# sch_station_de_charge.net
KiCad netlist of a schematic drawn in Altium Designer
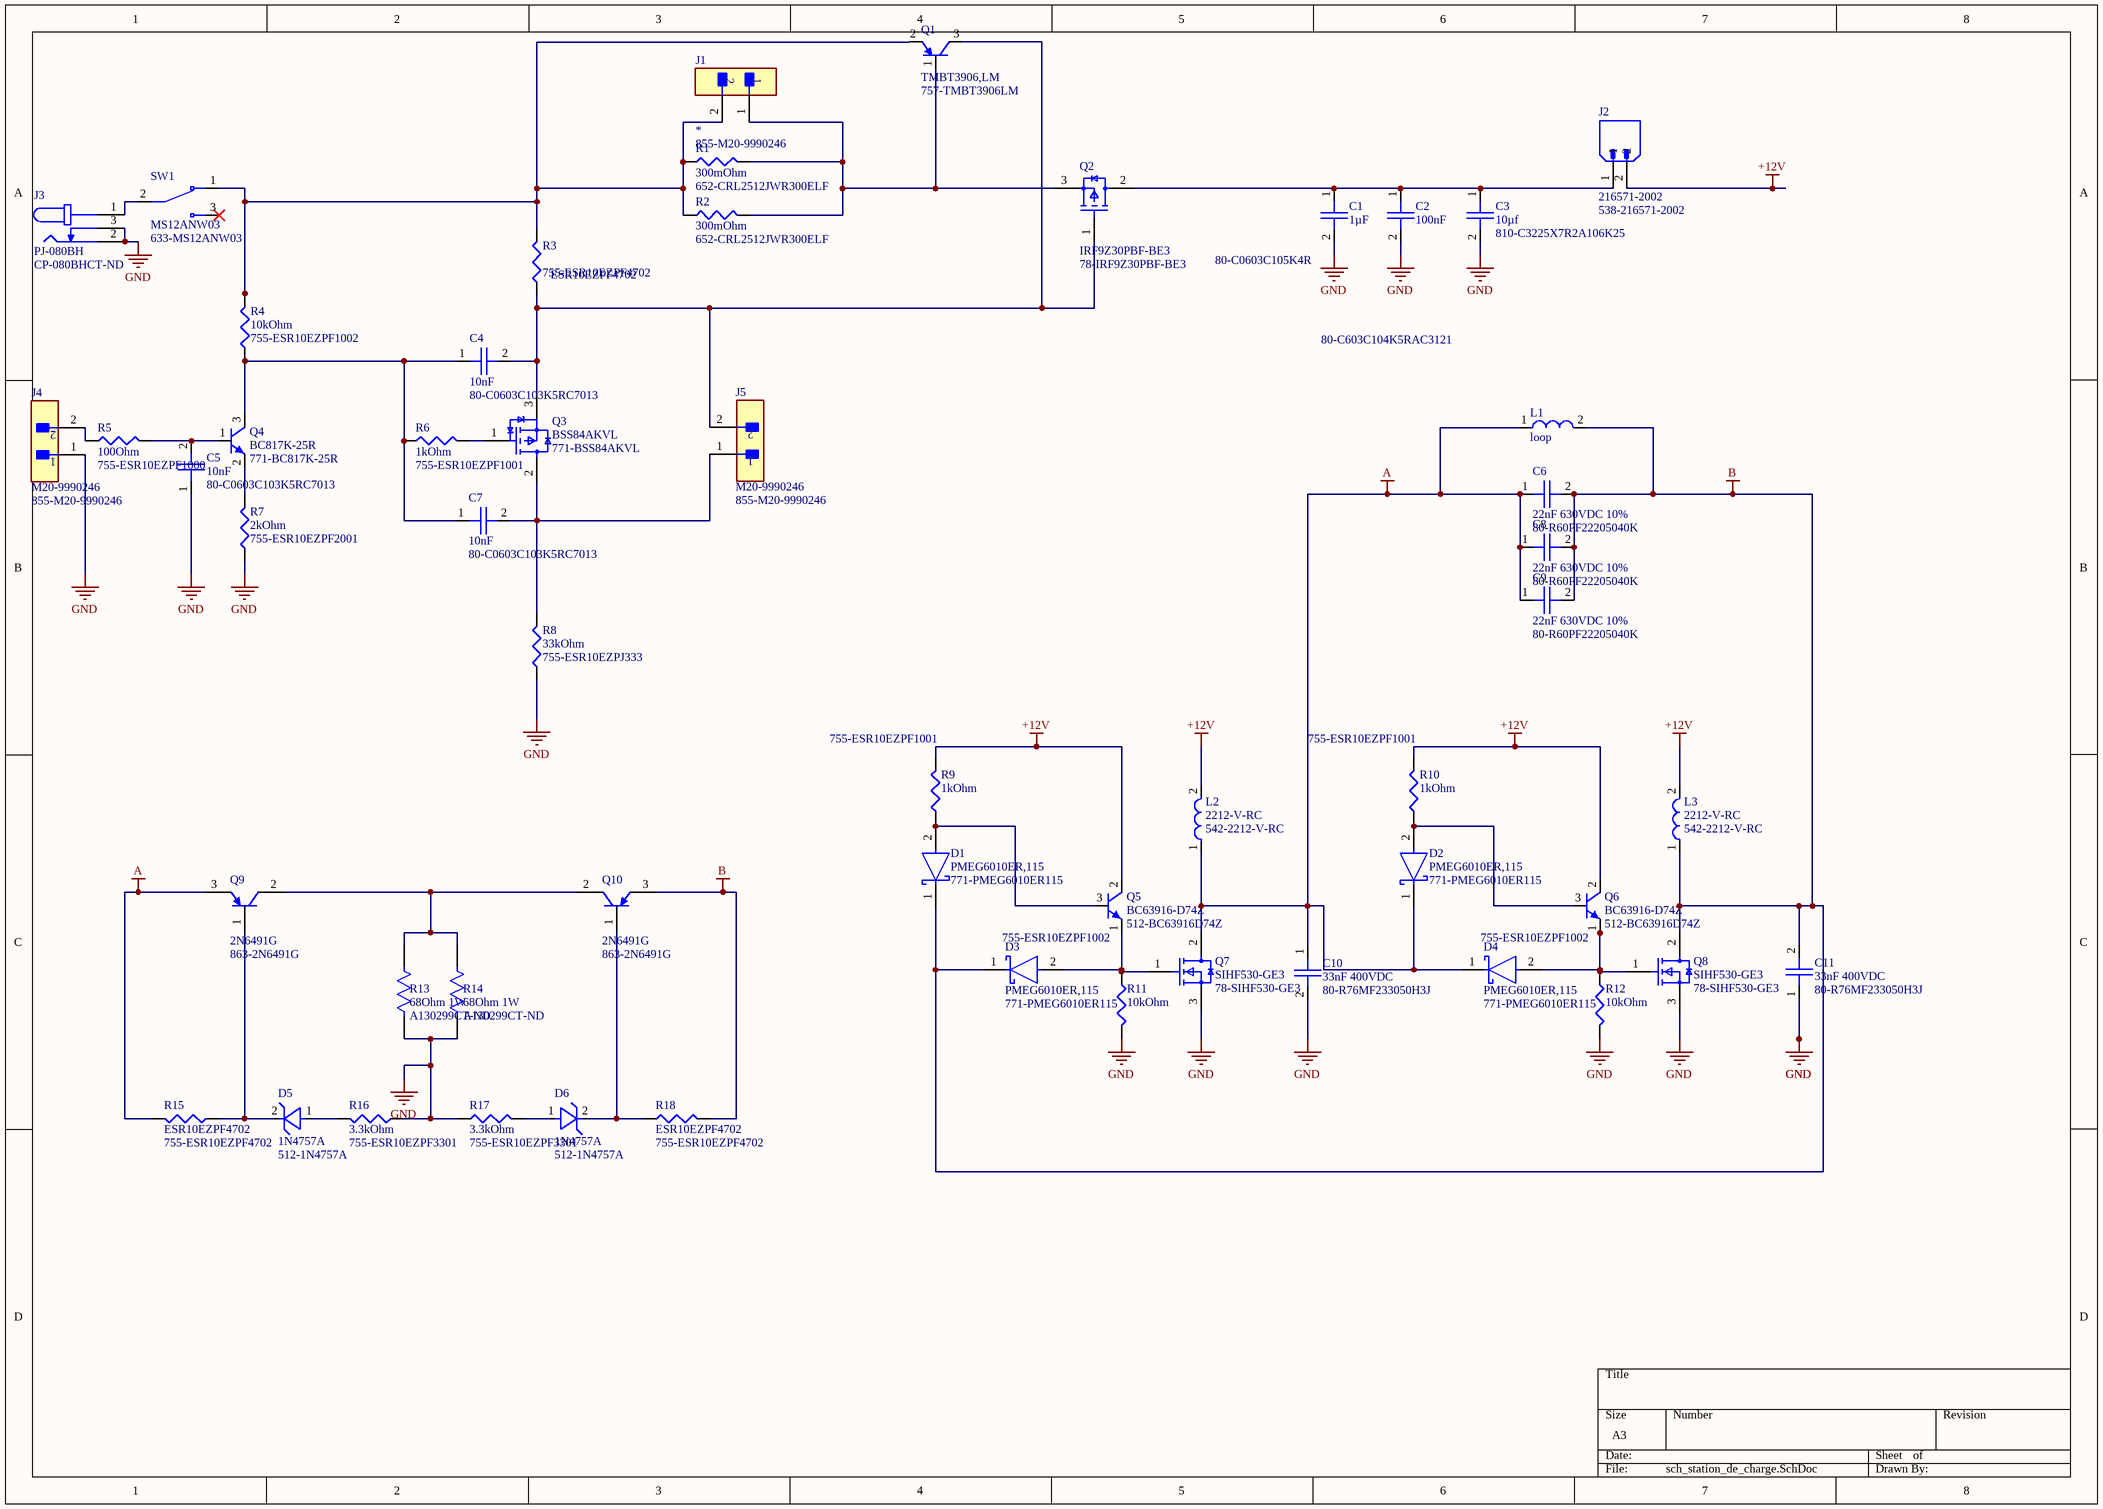
[diagram p0: sch_station_de_charge.SchDoc]

(export (version "E")
  (design (tool "Eeschema 10.0.6"))
  (components
    (comp (ref "C1")
      (value "1µF")
      (footprint "CAPC1608X90X35NL15T15")
      (description "Cap Ceramic 1uF 16V X7R 10% SMD 0603 125°C Paper T/R")
      (fields
        (field (name "MANUFACTURER") "KEMET")
        (field (name "MANUFACTURER PART NUMBER") "C0603C105K4RACTU")
        (field (name "SUPPLIER PART NUMBER 1") "80-C0603C105K4R")
      )
      (libsource (lib "station_de_charge_SchLib") (part "C0603C105K4RACTU"))
    )
    (comp (ref "C2")
      (value "100nF")
      (footprint "FP-C0603C104K5RAC3121-IPC_A")
      (description "Cap Ceramic 0.1uF 50V X7R 10% Pad SMD 0603 125°C T/R")
      (fields
        (field (name "MANUFACTURER") "KEMET")
        (field (name "MANUFACTURER PART NUMBER") "C0603C104K5RAC3121")
        (field (name "SUPPLIER PART NUMBER 1") "80-C603C104K5RAC3121")
      )
      (libsource (lib "lib_station_de_charge") (part "C0603C104K5RAC3121"))
    )
    (comp (ref "C3")
      (value "10µf")
      (footprint "CAPC3225X280N")
      (description "Multilayer Ceramic Chip Capacitors, Capacitance=10μF, LxWxT: 3.2x2.5x2.5mm")
      (fields
        (field (name "MANUFACTURER") "TDK")
        (field (name "MANUFACTURER PART NUMBER") "C3225X7R2A106K250AC")
        (field (name "SUPPLIER PART NUMBER 1") "810-C3225X7R2A106K25")
      )
      (libsource (lib "station_de_charge_SchLib") (part "C3225X7R2A106K250AC"))
    )
    (comp (ref "C4")
      (value "10nF")
      (footprint "FP-C0603C104K5RAC3121-IPC_A")
      (description "Cap Ceramic 0.01uF 50V X7R 10% Pad SMD 0603 125C T/R")
      (fields
        (field (name "MANUFACTURER") "KEMET")
        (field (name "MANUFACTURER PART NUMBER") "C0603C103K5RAC7013")
        (field (name "SUPPLIER PART NUMBER 1") "80-C0603C103K5RC7013")
      )
      (libsource (lib "station_de_charge_SchLib") (part "C0603C103K5RAC7013"))
    )
    (comp (ref "C5")
      (value "10nF")
      (footprint "FP-C0603C104K5RAC3121-IPC_A")
      (description "Cap Ceramic 0.01uF 50V X7R 10% Pad SMD 0603 125C T/R")
      (fields
        (field (name "MANUFACTURER") "KEMET")
        (field (name "MANUFACTURER PART NUMBER") "C0603C103K5RAC7013")
        (field (name "SUPPLIER PART NUMBER 1") "80-C0603C103K5RC7013")
      )
      (libsource (lib "station_de_charge_SchLib") (part "C0603C103K5RAC7013"))
    )
    (comp (ref "C6")
      (value "22nF 630VDC 10%")
      (footprint "R60PF22205040K")
      (description "Cap Film 0.022uF 630V PET 10%( 13 X 4 X 9mm) Radial Wound 10mm 105C Automotive Bag")
      (fields
        (field (name "MANUFACTURER") "KEMET")
        (field (name "MANUFACTURER PART NUMBER") "R60PF22205040K")
        (field (name "SUPPLIER PART NUMBER 1") "80-R60PF22205040K")
      )
      (libsource (lib "station_de_charge_SchLib") (part "R60PF22205040K"))
    )
    (comp (ref "C7")
      (value "10nF")
      (footprint "FP-C0603C104K5RAC3121-IPC_A")
      (description "Cap Ceramic 0.01uF 50V X7R 10% Pad SMD 0603 125C T/R")
      (fields
        (field (name "MANUFACTURER") "KEMET")
        (field (name "MANUFACTURER PART NUMBER") "C0603C103K5RAC7013")
        (field (name "SUPPLIER PART NUMBER 1") "80-C0603C103K5RC7013")
      )
      (libsource (lib "station_de_charge_SchLib") (part "C0603C103K5RAC7013"))
    )
    (comp (ref "C8")
      (value "22nF 630VDC 10%")
      (footprint "R60PF22205040K")
      (description "Cap Film 0.022uF 630V PET 10%( 13 X 4 X 9mm) Radial Wound 10mm 105C Automotive Bag")
      (fields
        (field (name "MANUFACTURER") "KEMET")
        (field (name "MANUFACTURER PART NUMBER") "R60PF22205040K")
        (field (name "SUPPLIER PART NUMBER 1") "80-R60PF22205040K")
      )
      (libsource (lib "station_de_charge_SchLib") (part "R60PF22205040K"))
    )
    (comp (ref "C9")
      (value "22nF 630VDC 10%")
      (footprint "R60PF22205040K")
      (description "Cap Film 0.022uF 630V PET 10%( 13 X 4 X 9mm) Radial Wound 10mm 105C Automotive Bag")
      (fields
        (field (name "MANUFACTURER") "KEMET")
        (field (name "MANUFACTURER PART NUMBER") "R60PF22205040K")
        (field (name "SUPPLIER PART NUMBER 1") "80-R60PF22205040K")
      )
      (libsource (lib "station_de_charge_SchLib") (part "R60PF22205040K"))
    )
    (comp (ref "C10")
      (value "33nF 400VDC")
      (footprint "R60PF22205040K")
      (description "Double Metallized Polypropylene Film Capacitor")
      (fields
        (field (name "MANUFACTURER") "KEMET")
        (field (name "MANUFACTURER PART NUMBER") "R76MF233050H3J")
        (field (name "SUPPLIER PART NUMBER 1") "80-R76MF233050H3J")
      )
      (libsource (lib "station_de_charge_SchLib") (part "R76MF233050H3J"))
    )
    (comp (ref "C11")
      (value "33nF 400VDC")
      (footprint "R60PF22205040K")
      (description "Double Metallized Polypropylene Film Capacitor")
      (fields
        (field (name "MANUFACTURER") "KEMET")
        (field (name "MANUFACTURER PART NUMBER") "R76MF233050H3J")
        (field (name "SUPPLIER PART NUMBER 1") "80-R76MF233050H3J")
      )
      (libsource (lib "station_de_charge_SchLib") (part "R76MF233050H3J"))
    )
    (comp (ref "D1")
      (value "PMEG6010ER,115")
      (footprint "TVS_PTVS13VS1UR,115")
      (description "DIODE SCHOTTKY 60V 1A SOD123W")
      (fields
        (field (name "MANUFACTURER") "Nexperia")
        (field (name "SUPPLIER PART NUMBER 1") "771-PMEG6010ER115")
      )
      (libsource (lib "station_de_charge_SchLib") (part "PMEG6010ER,115"))
    )
    (comp (ref "D2")
      (value "PMEG6010ER,115")
      (footprint "TVS_PTVS13VS1UR,115")
      (description "DIODE SCHOTTKY 60V 1A SOD123W")
      (fields
        (field (name "MANUFACTURER") "Nexperia")
        (field (name "SUPPLIER PART NUMBER 1") "771-PMEG6010ER115")
      )
      (libsource (lib "station_de_charge_SchLib") (part "PMEG6010ER,115"))
    )
    (comp (ref "D3")
      (value "PMEG6010ER,115")
      (footprint "TVS_PTVS13VS1UR,115")
      (description "DIODE SCHOTTKY 60V 1A SOD123W")
      (fields
        (field (name "MANUFACTURER") "Nexperia")
        (field (name "SUPPLIER PART NUMBER 1") "771-PMEG6010ER115")
      )
      (libsource (lib "station_de_charge_SchLib") (part "PMEG6010ER,115"))
    )
    (comp (ref "D4")
      (value "PMEG6010ER,115")
      (footprint "TVS_PTVS13VS1UR,115")
      (description "DIODE SCHOTTKY 60V 1A SOD123W")
      (fields
        (field (name "MANUFACTURER") "Nexperia")
        (field (name "SUPPLIER PART NUMBER 1") "771-PMEG6010ER115")
      )
      (libsource (lib "station_de_charge_SchLib") (part "PMEG6010ER,115"))
    )
    (comp (ref "D5")
      (value "1N4757A")
      (footprint "FAIR-DO-41-2_V")
      (description "Diode Zener Single 51V 5% 1000mW 2-Pin DO-41")
      (fields
        (field (name "MANUFACTURER") "ON Semiconductor / Fairchild")
        (field (name "TOLERANCE") "5%")
        (field (name "SUPPLIER PART NUMBER 1") "512-1N4757A")
      )
      (libsource (lib "station_de_charge_SchLib") (part "1N4757A"))
    )
    (comp (ref "D6")
      (value "1N4757A")
      (footprint "FAIR-DO-41-2_V")
      (description "Diode Zener Single 51V 5% 1000mW 2-Pin DO-41")
      (fields
        (field (name "MANUFACTURER") "ON Semiconductor / Fairchild")
        (field (name "TOLERANCE") "5%")
        (field (name "SUPPLIER PART NUMBER 1") "512-1N4757A")
      )
      (libsource (lib "station_de_charge_SchLib") (part "1N4757A"))
    )
    (comp (ref "J1")
      (value "*")
      (footprint "FP-M20-9990246-MFG")
      (description "2.54mm (0.1\") Pitch SIL Vertical PC Tail Pin Header, 6.1mm mating pin height, tin, 2 contacts")
      (fields
        (field (name "MANUFACTURER") "Harwin")
        (field (name "MANUFACTURER PART NUMBER") "M20-9990246")
        (field (name "SUPPLIER PART NUMBER 1") "855-M20-9990246")
      )
      (libsource (lib "*") (part "M20-9990246"))
    )
    (comp (ref "J2")
      (value "216571-2002")
      (footprint "MOLEX_2165712002")
      (description "Connector Power Header 2Position 3mm PC Pin Straight Through Hole 2 Terminal 1 Port Tray")
      (fields (field (name "MANUFACTURER") "Molex") (field (name "SUPPLIER PART NUMBER 1") "538-216571-2002"))
      (libsource (lib "station_de_charge_SchLib") (part "216571-2002"))
    )
    (comp (ref "J3")
      (value "PJ-080BH")
      (footprint "CUI_PJ-080BH")
      (description "Power Barrel Connector Jack 2.50mm ID (0.098\"), 5.50mm OD (0.217\") Through Hole,")
      (fields (field (name "MANUFACTURER") "CUI") (field (name "SUPPLIER PART NUMBER 1") "CP-080BHCT-ND"))
      (libsource (lib "station_de_charge_SchLib") (part "PJ-080BH"))
    )
    (comp (ref "J4")
      (value "M20-9990246")
      (footprint "FP-M20-9990246-MFG")
      (description "2.54mm (0.1\") Pitch SIL Vertical PC Tail Pin Header, 6.1mm mating pin height, tin, 2 contacts")
      (fields
        (field (name "MANUFACTURER") "Harwin")
        (field (name "SUPPLIER PART NUMBER 1") "855-M20-9990246")
      )
      (libsource (lib "station_de_charge_SchLib") (part "M20-9990246"))
    )
    (comp (ref "J5")
      (value "M20-9990246")
      (footprint "FP-M20-9990246-MFG")
      (description "2.54mm (0.1\") Pitch SIL Vertical PC Tail Pin Header, 6.1mm mating pin height, tin, 2 contacts")
      (fields
        (field (name "MANUFACTURER") "Harwin")
        (field (name "SUPPLIER PART NUMBER 1") "855-M20-9990246")
      )
      (libsource (lib "") (part "M20-9990246_1"))
    )
    (comp (ref "L1")
      (value "loop")
      (footprint "loop")
      (libsource (lib "station_de_charge_SchLib") (part "loop"))
    )
    (comp (ref "L2")
      (value "2212-V-RC")
      (footprint "IND_HCTI-220-5.8")
      (description "Inductor High Current Toroid 100uH/64uH 15% 1KHz 4.4A 56mOhm DCR RDL")
      (fields
        (field (name "MANUFACTURER") "Bourns JW Miller")
        (field (name "TOLERANCE") "15%")
        (field (name "SUPPLIER PART NUMBER 1") "542-2212-V-RC")
      )
      (libsource (lib "station_de_charge_SchLib") (part "2212-V-RC"))
    )
    (comp (ref "L3")
      (value "2212-V-RC")
      (footprint "IND_HCTI-220-5.8")
      (description "Inductor High Current Toroid 100uH/64uH 15% 1KHz 4.4A 56mOhm DCR RDL")
      (fields
        (field (name "MANUFACTURER") "Bourns JW Miller")
        (field (name "TOLERANCE") "15%")
        (field (name "SUPPLIER PART NUMBER 1") "542-2212-V-RC")
      )
      (libsource (lib "station_de_charge_SchLib") (part "2212-V-RC"))
    )
    (comp (ref "Q1")
      (value "TMBT3906,LM")
      (footprint "FP-TMBT3906")
      (description "TRANSPNP50V0.15ASOT23-3")
      (fields
        (field (name "MANUFACTURER") "Toshiba")
        (field (name "SUPPLIER PART NUMBER 1") "757-TMBT3906LM")
      )
      (libsource (lib "station_de_charge_SchLib") (part "TMBT3906,LM"))
    )
    (comp (ref "Q2")
      (value "IRF9Z30PBF-BE3")
      (footprint "TO-220AB-3-package")
      (fields
        (field (name "MANUFACTURER") "Vishay Siliconix")
        (field (name "SUPPLIER PART NUMBER 1") "78-IRF9Z30PBF-BE3")
      )
      (libsource (lib "station_de_charge_SchLib") (part "IRF9Z30PBF-BE3"))
    )
    (comp (ref "Q3")
      (value "BSS84AKVL")
      (footprint "SOT95P230X110-3N")
      (description "BSS84AKV/SOT666/SOT6")
      (fields
        (field (name "MANUFACTURER") "Nexperia")
        (field (name "SUPPLIER PART NUMBER 1") "771-BSS84AKVL")
      )
      (libsource (lib "station_de_charge_SchLib") (part "BSS84AKVL"))
    )
    (comp (ref "Q4")
      (value "BC817K-25R")
      (footprint "SOT95P230X110-3N")
      (description "BC817K-25H/SOT23/TO-236AB")
      (fields
        (field (name "MANUFACTURER") "Nexperia")
        (field (name "SUPPLIER PART NUMBER 1") "771-BC817K-25R")
      )
      (libsource (lib "station_de_charge_SchLib") (part "BC817K-25R"))
    )
    (comp (ref "Q5")
      (value "BC63916-D74Z")
      (footprint "TO92127P478H483-3")
      (description "NPN Medium Power Transistor")
      (fields
        (field (name "MANUFACTURER") "ON Semiconductor / Fairchild")
        (field (name "SUPPLIER PART NUMBER 1") "512-BC63916D74Z")
      )
      (libsource (lib "station_de_charge_SchLib") (part "BC63916-D74Z"))
    )
    (comp (ref "Q6")
      (value "BC63916-D74Z")
      (footprint "TO92127P478H483-3")
      (description "NPN Medium Power Transistor")
      (fields
        (field (name "MANUFACTURER") "ON Semiconductor / Fairchild")
        (field (name "SUPPLIER PART NUMBER 1") "512-BC63916D74Z")
      )
      (libsource (lib "station_de_charge_SchLib") (part "BC63916-D74Z"))
    )
    (comp (ref "Q7")
      (value "SIHF530-GE3")
      (footprint "FP-SIHF530-GE3")
      (fields (field (name "MANUFACTURER") "Vishay") (field (name "SUPPLIER PART NUMBER 1") "78-SIHF530-GE3"))
      (libsource (lib "station_de_charge_SchLib") (part "SIHF530-GE3"))
    )
    (comp (ref "Q8")
      (value "SIHF530-GE3")
      (footprint "FP-SIHF530-GE3")
      (fields (field (name "MANUFACTURER") "Vishay") (field (name "SUPPLIER PART NUMBER 1") "78-SIHF530-GE3"))
      (libsource (lib "station_de_charge_SchLib") (part "SIHF530-GE3"))
    )
    (comp (ref "Q9")
      (value "2N6491G")
      (footprint "ONSC-TO-220-3-221A-09")
      (description "Power Bipolar Transistor, 15A, 8")
      (fields
        (field (name "MANUFACTURER") "ON Semiconductor")
        (field (name "SUPPLIER PART NUMBER 1") "863-2N6491G")
      )
      (libsource (lib "station_de_charge_SchLib") (part "2N6491G"))
    )
    (comp (ref "Q10")
      (value "2N6491G")
      (footprint "ONSC-TO-220-3-221A-09")
      (description "Power Bipolar Transistor, 15A, 8")
      (fields
        (field (name "MANUFACTURER") "ON Semiconductor")
        (field (name "SUPPLIER PART NUMBER 1") "863-2N6491G")
      )
      (libsource (lib "station_de_charge_SchLib") (part "2N6491G"))
    )
    (comp (ref "R1")
      (value "300mOhm")
      (footprint "RESC6331X70N")
      (description "Res Thick Film 2512 0.3 Ohm 5% 1W ±200ppm/°C Molded SMD SMD Embossed Plastic T/R")
      (fields
        (field (name "MANUFACTURER") "Bourns")
        (field (name "MANUFACTURER PART NUMBER") "CRL2512-JW-R300ELF")
        (field (name "SUPPLIER PART NUMBER 1") "652-CRL2512JWR300ELF")
      )
      (libsource (lib "station_de_charge_SchLib") (part "CRL2512-JW-R300ELF"))
    )
    (comp (ref "R2")
      (value "300mOhm")
      (footprint "RESC6331X70N")
      (description "Res Thick Film 2512 0.3 Ohm 5% 1W ±200ppm/°C Molded SMD SMD Embossed Plastic T/R")
      (fields
        (field (name "MANUFACTURER") "Bourns")
        (field (name "MANUFACTURER PART NUMBER") "CRL2512-JW-R300ELF")
        (field (name "SUPPLIER PART NUMBER 1") "652-CRL2512JWR300ELF")
      )
      (libsource (lib "station_de_charge_SchLib") (part "CRL2512-JW-R300ELF"))
    )
    (comp (ref "R3")
      (value "ESR10EZPF4702")
      (footprint "FP-ESR10-IPC_A")
      (description "Res Thick Film 0805 47K Ohm 1% 0.4W ±100ppm/C Pad SMD Automotive T/R")
      (fields
        (field (name "MANUFACTURER") "Rohm")
        (field (name "TOLERANCE") "1%")
        (field (name "SUPPLIER PART NUMBER 1") "755-ESR10EZPF4702")
      )
      (libsource (lib "station_de_charge_SchLib") (part "ESR10EZPF4702"))
    )
    (comp (ref "R4")
      (value "10kOhm")
      (footprint "FP-ESR10-IPC_A")
      (description "Res Thick Film 0805 10K Ohm 1% 0.4W ±100ppm/C Pad SMD Automotive T/R")
      (fields
        (field (name "MANUFACTURER") "Rohm")
        (field (name "MANUFACTURER PART NUMBER") "ESR10EZPF1002")
        (field (name "SUPPLIER PART NUMBER 1") "755-ESR10EZPF1002")
      )
      (libsource (lib "station_de_charge_SchLib") (part "ESR10EZPF1002"))
    )
    (comp (ref "R5")
      (value "100Ohm")
      (footprint "FP-ESR10-IPC_A")
      (description "Res Thick Film 0805 100 Ohm 1% 2/5W ±100ppm/°C Molded SMD Paper T/R")
      (fields
        (field (name "MANUFACTURER") "Rohm")
        (field (name "MANUFACTURER PART NUMBER") "ESR10EZPF1000")
        (field (name "SUPPLIER PART NUMBER 1") "755-ESR10EZPF1000")
      )
      (libsource (lib "station_de_charge_SchLib") (part "ESR10EZPF1000"))
    )
    (comp (ref "R6")
      (value "1kOhm")
      (footprint "FP-ESR10-IPC_A")
      (description "Res Thick Film 0805 1K Ohm 1% 0.4W ±100ppm/C Epoxy Resin Pad SMD Automotive T/R")
      (fields
        (field (name "MANUFACTURER") "Rohm")
        (field (name "MANUFACTURER PART NUMBER") "ESR10EZPF1001")
        (field (name "SUPPLIER PART NUMBER 1") "755-ESR10EZPF1001")
      )
      (libsource (lib "station_de_charge_SchLib") (part "ESR10EZPF1001"))
    )
    (comp (ref "R7")
      (value "2kOhm")
      (footprint "FP-ESR10-IPC_A")
      (description "Res Thick Film 0805 2K Ohm 1% 2/5W ±100ppm/°C Molded SMD Paper T/R")
      (fields
        (field (name "MANUFACTURER") "Rohm")
        (field (name "MANUFACTURER PART NUMBER") "ESR10EZPF2001")
        (field (name "SUPPLIER PART NUMBER 1") "755-ESR10EZPF2001")
      )
      (libsource (lib "station_de_charge_SchLib") (part "ESR10EZPF2001"))
    )
    (comp (ref "R8")
      (value "33kOhm")
      (footprint "FP-ESR10-IPC_A")
      (description "Res Thick Film 0805 33K Ohm 5% 0.4W ±200ppm/C Pad SMD Automotive T/R")
      (fields
        (field (name "MANUFACTURER") "Rohm")
        (field (name "MANUFACTURER PART NUMBER") "ESR10EZPJ333")
        (field (name "SUPPLIER PART NUMBER 1") "755-ESR10EZPJ333")
      )
      (libsource (lib "station_de_charge_SchLib") (part "ESR10EZPJ333"))
    )
    (comp (ref "R9")
      (value "1kOhm")
      (footprint "FP-ESR10-IPC_A")
      (description "Res Thick Film 0805 1K Ohm 1% 0.4W ±100ppm/C Epoxy Resin Pad SMD Automotive T/R")
      (fields
        (field (name "MANUFACTURER") "Rohm")
        (field (name "MANUFACTURER PART NUMBER") "ESR10EZPF1001")
        (field (name "SUPPLIER PART NUMBER 1") "755-ESR10EZPF1001")
      )
      (libsource (lib "lib_station_de_charge") (part "ESR10EZPF1001"))
    )
    (comp (ref "R10")
      (value "1kOhm")
      (footprint "FP-ESR10-IPC_A")
      (description "Res Thick Film 0805 1K Ohm 1% 0.4W ±100ppm/C Epoxy Resin Pad SMD Automotive T/R")
      (fields
        (field (name "MANUFACTURER") "Rohm")
        (field (name "MANUFACTURER PART NUMBER") "ESR10EZPF1001")
        (field (name "SUPPLIER PART NUMBER 1") "755-ESR10EZPF1001")
      )
      (libsource (lib "lib_station_de_charge") (part "ESR10EZPF1001"))
    )
    (comp (ref "R11")
      (value "10kOhm")
      (footprint "FP-ESR10-IPC_A")
      (description "Res Thick Film 0805 10K Ohm 1% 0.4W ±100ppm/C Pad SMD Automotive T/R")
      (fields
        (field (name "MANUFACTURER") "Rohm")
        (field (name "MANUFACTURER PART NUMBER") "ESR10EZPF1002")
        (field (name "SUPPLIER PART NUMBER 1") "755-ESR10EZPF1002")
      )
      (libsource (lib "lib_station_de_charge") (part "ESR10EZPF1002"))
    )
    (comp (ref "R12")
      (value "10kOhm")
      (footprint "FP-ESR10-IPC_A")
      (description "Res Thick Film 0805 10K Ohm 1% 0.4W ±100ppm/C Pad SMD Automotive T/R")
      (fields
        (field (name "MANUFACTURER") "Rohm")
        (field (name "MANUFACTURER PART NUMBER") "ESR10EZPF1002")
        (field (name "SUPPLIER PART NUMBER 1") "755-ESR10EZPF1002")
      )
      (libsource (lib "lib_station_de_charge") (part "ESR10EZPF1002"))
    )
    (comp (ref "R13")
      (value "68Ohm 1W")
      (footprint "FP-CRGCQ2512-IPC_A")
      (description "Res General Purpose Thick Film 2512 68 Ohm 5% 1W ±200ppm/°C Molded Emboss T/R")
      (fields
        (field (name "MANUFACTURER") "TE Connectivity")
        (field (name "MANUFACTURER PART NUMBER") "CRGCQ2512J68R")
        (field (name "SUPPLIER PART NUMBER 1") "A130299CT-ND")
      )
      (libsource (lib "station_de_charge_SchLib") (part "CRGCQ2512J68R"))
    )
    (comp (ref "R14")
      (value "68Ohm 1W")
      (footprint "FP-CRGCQ2512-IPC_A")
      (description "Res General Purpose Thick Film 2512 68 Ohm 5% 1W ±200ppm/°C Molded Emboss T/R")
      (fields
        (field (name "MANUFACTURER") "TE Connectivity")
        (field (name "MANUFACTURER PART NUMBER") "CRGCQ2512J68R")
        (field (name "SUPPLIER PART NUMBER 1") "A130299CT-ND")
      )
      (libsource (lib "station_de_charge_SchLib") (part "CRGCQ2512J68R"))
    )
    (comp (ref "R15")
      (value "ESR10EZPF4702")
      (footprint "FP-ESR10-IPC_A")
      (description "Res Thick Film 0805 47K Ohm 1% 0.4W ±100ppm/C Pad SMD Automotive T/R")
      (fields
        (field (name "MANUFACTURER") "Rohm")
        (field (name "TOLERANCE") "1%")
        (field (name "SUPPLIER PART NUMBER 1") "755-ESR10EZPF4702")
      )
      (libsource (lib "station_de_charge_SchLib") (part "ESR10EZPF4702"))
    )
    (comp (ref "R16")
      (value "3.3kOhm")
      (footprint "FP-ESR10-IPC_A")
      (description "Res Thick Film 0805 3.3K Ohm 1% 2/5W ±100ppm/°C Molded SMD SMD Paper T/R")
      (fields
        (field (name "MANUFACTURER") "Rohm")
        (field (name "MANUFACTURER PART NUMBER") "ESR10EZPF3301")
        (field (name "SUPPLIER PART NUMBER 1") "755-ESR10EZPF3301")
      )
      (libsource (lib "station_de_charge_SchLib") (part "ESR10EZPF3301"))
    )
    (comp (ref "R17")
      (value "3.3kOhm")
      (footprint "FP-ESR10-IPC_A")
      (description "Res Thick Film 0805 3.3K Ohm 1% 2/5W ±100ppm/°C Molded SMD SMD Paper T/R")
      (fields
        (field (name "MANUFACTURER") "Rohm")
        (field (name "MANUFACTURER PART NUMBER") "ESR10EZPF3301")
        (field (name "SUPPLIER PART NUMBER 1") "755-ESR10EZPF3301")
      )
      (libsource (lib "station_de_charge_SchLib") (part "ESR10EZPF3301"))
    )
    (comp (ref "R18")
      (value "ESR10EZPF4702")
      (footprint "FP-ESR10-IPC_A")
      (description "Res Thick Film 0805 47K Ohm 1% 0.4W ±100ppm/C Pad SMD Automotive T/R")
      (fields
        (field (name "MANUFACTURER") "Rohm")
        (field (name "TOLERANCE") "1%")
        (field (name "SUPPLIER PART NUMBER 1") "755-ESR10EZPF4702")
      )
      (libsource (lib "station_de_charge_SchLib") (part "ESR10EZPF4702"))
    )
    (comp (ref "SW1")
      (value "MS12ANW03")
      (footprint "SW_MS12ANW03")
      (description "Switch Slide ON None ON SPDT Top Slide 6A 250VAC 100000Cycles PC Pins Thru-Hole")
      (fields
        (field (name "MANUFACTURER") "NKK Switches")
        (field (name "SUPPLIER PART NUMBER 1") "633-MS12ANW03")
      )
      (libsource (lib "station_de_charge_SchLib") (part "MS12ANW03"))
    )
  )
  (nets
    (net (code "1") (name "+12V") (class "Default")
      (node (ref "J2") (pin "2") (pinfunction "2_2") (pintype "passive"))
      (node (ref "L2") (pin "2") (pinfunction "2_2") (pintype "passive"))
      (node (ref "L3") (pin "2") (pinfunction "2_2") (pintype "passive"))
      (node (ref "Q5") (pin "2") (pinfunction "C_2") (pintype "passive"))
      (node (ref "Q6") (pin "2") (pinfunction "C_2") (pintype "passive"))
      (node (ref "R10") (pin "2") (pinfunction "2_2") (pintype "passive"))
      (node (ref "R9") (pin "2") (pinfunction "2_2") (pintype "passive"))
    )
    (net (code "2") (name "A") (class "Default")
      (node (ref "C10") (pin "1") (pinfunction "1_1") (pintype "passive"))
      (node (ref "C6") (pin "1") (pinfunction "1_1") (pintype "passive"))
      (node (ref "C8") (pin "1") (pinfunction "1_1") (pintype "passive"))
      (node (ref "C9") (pin "1") (pinfunction "1_1") (pintype "passive"))
      (node (ref "D2") (pin "1") (pinfunction "C_1") (pintype "passive"))
      (node (ref "D4") (pin "1") (pinfunction "C_1") (pintype "passive"))
      (node (ref "L1") (pin "1") (pinfunction "1_1") (pintype "passive"))
      (node (ref "L2") (pin "1") (pinfunction "1_1") (pintype "passive"))
      (node (ref "Q7") (pin "2") (pinfunction "DRAIN_2") (pintype "passive"))
      (node (ref "Q9") (pin "3") (pinfunction "E_3") (pintype "passive"))
      (node (ref "R15") (pin "2") (pinfunction "2_2") (pintype "passive"))
    )
    (net (code "3") (name "B") (class "Default")
      (node (ref "C11") (pin "2") (pinfunction "2_2") (pintype "passive"))
      (node (ref "C6") (pin "2") (pinfunction "2_2") (pintype "passive"))
      (node (ref "C8") (pin "2") (pinfunction "2_2") (pintype "passive"))
      (node (ref "C9") (pin "2") (pinfunction "2_2") (pintype "passive"))
      (node (ref "D1") (pin "1") (pinfunction "C_1") (pintype "passive"))
      (node (ref "D3") (pin "1") (pinfunction "C_1") (pintype "passive"))
      (node (ref "L1") (pin "2") (pinfunction "2_2") (pintype "passive"))
      (node (ref "L3") (pin "1") (pinfunction "1_1") (pintype "passive"))
      (node (ref "Q10") (pin "3") (pinfunction "E_3") (pintype "passive"))
      (node (ref "Q8") (pin "2") (pinfunction "DRAIN_2") (pintype "passive"))
      (node (ref "R18") (pin "2") (pinfunction "2_2") (pintype "passive"))
    )
    (net (code "4") (name "GND") (class "Default")
      (node (ref "C1") (pin "2") (pinfunction "2_2") (pintype "passive"))
      (node (ref "C10") (pin "2") (pinfunction "2_2") (pintype "passive"))
      (node (ref "C11") (pin "1") (pinfunction "1_1") (pintype "passive"))
      (node (ref "C2") (pin "2") (pinfunction "2_2") (pintype "passive"))
      (node (ref "C3") (pin "2") (pinfunction "2_2") (pintype "passive"))
      (node (ref "C5") (pin "1") (pinfunction "1_1") (pintype "passive"))
      (node (ref "J3") (pin "2") (pinfunction "2_2") (pintype "passive"))
      (node (ref "J3") (pin "3") (pinfunction "3_3") (pintype "passive"))
      (node (ref "J4") (pin "1") (pinfunction "1_1") (pintype "passive"))
      (node (ref "Q7") (pin "3") (pinfunction "SOURCE_3") (pintype "passive"))
      (node (ref "Q8") (pin "3") (pinfunction "SOURCE_3") (pintype "passive"))
      (node (ref "R11") (pin "2") (pinfunction "2_2") (pintype "passive"))
      (node (ref "R12") (pin "2") (pinfunction "2_2") (pintype "passive"))
      (node (ref "R13") (pin "1") (pinfunction "1_1") (pintype "passive"))
      (node (ref "R14") (pin "1") (pinfunction "1_1") (pintype "passive"))
      (node (ref "R16") (pin "1") (pinfunction "1_1") (pintype "passive"))
      (node (ref "R17") (pin "1") (pinfunction "1_1") (pintype "passive"))
      (node (ref "R7") (pin "1") (pinfunction "1_1") (pintype "passive"))
      (node (ref "R8") (pin "1") (pinfunction "1_1") (pintype "passive"))
    )
    (net (code "5") (name "Net-(D1-A)") (class "Default")
      (node (ref "D1") (pin "2") (pinfunction "A_2") (pintype "passive"))
      (node (ref "Q5") (pin "3") (pinfunction "B_3") (pintype "passive"))
      (node (ref "R9") (pin "1") (pinfunction "1_1") (pintype "passive"))
    )
    (net (code "6") (name "Net-(D2-A)") (class "Default")
      (node (ref "D2") (pin "2") (pinfunction "A_2") (pintype "passive"))
      (node (ref "Q6") (pin "3") (pinfunction "B_3") (pintype "passive"))
      (node (ref "R10") (pin "1") (pinfunction "1_1") (pintype "passive"))
    )
    (net (code "7") (name "Net-(D3-A)") (class "Default")
      (node (ref "D3") (pin "2") (pinfunction "A_2") (pintype "passive"))
      (node (ref "Q5") (pin "1") (pinfunction "E_1") (pintype "passive"))
      (node (ref "Q7") (pin "1") (pinfunction "GATE_1") (pintype "passive"))
      (node (ref "R11") (pin "1") (pinfunction "1_1") (pintype "passive"))
    )
    (net (code "8") (name "Net-(D4-A)") (class "Default")
      (node (ref "D4") (pin "2") (pinfunction "A_2") (pintype "passive"))
      (node (ref "Q6") (pin "1") (pinfunction "E_1") (pintype "passive"))
      (node (ref "Q8") (pin "1") (pinfunction "GATE_1") (pintype "passive"))
      (node (ref "R12") (pin "1") (pinfunction "1_1") (pintype "passive"))
    )
    (net (code "9") (name "Net-(D5-A)") (class "Default")
      (node (ref "D5") (pin "1") (pinfunction "A_1") (pintype "passive"))
      (node (ref "R16") (pin "2") (pinfunction "2_2") (pintype "passive"))
    )
    (net (code "10") (name "Net-(D5-K)") (class "Default")
      (node (ref "D5") (pin "2") (pinfunction "K_2") (pintype "passive"))
      (node (ref "Q9") (pin "1") (pinfunction "B_1") (pintype "passive"))
      (node (ref "R15") (pin "1") (pinfunction "1_1") (pintype "passive"))
    )
    (net (code "11") (name "Net-(D6-A)") (class "Default")
      (node (ref "D6") (pin "1") (pinfunction "A_1") (pintype "passive"))
      (node (ref "R17") (pin "2") (pinfunction "2_2") (pintype "passive"))
    )
    (net (code "12") (name "Net-(D6-K)") (class "Default")
      (node (ref "D6") (pin "2") (pinfunction "K_2") (pintype "passive"))
      (node (ref "Q10") (pin "1") (pinfunction "B_1") (pintype "passive"))
      (node (ref "R18") (pin "1") (pinfunction "1_1") (pintype "passive"))
    )
    (net (code "13") (name "Net-(J3-Pad1)") (class "Default")
      (node (ref "J3") (pin "1") (pinfunction "1_1") (pintype "passive"))
      (node (ref "SW1") (pin "2") (pinfunction "2_2") (pintype "passive"))
    )
    (net (code "14") (name "Net-(J4-Pad2)") (class "Default")
      (node (ref "J4") (pin "2") (pinfunction "2_2") (pintype "passive"))
      (node (ref "R5") (pin "1") (pinfunction "1_1") (pintype "passive"))
    )
    (net (code "15") (name "Net-(Q1-B)") (class "Default")
      (node (ref "J1") (pin "1") (pinfunction "1_1") (pintype "passive"))
      (node (ref "Q1") (pin "1") (pinfunction "B_1") (pintype "passive"))
      (node (ref "Q2") (pin "3") (pinfunction "SOURCE_3") (pintype "passive"))
      (node (ref "R1") (pin "2") (pinfunction "2_2") (pintype "passive"))
      (node (ref "R2") (pin "2") (pinfunction "2_2") (pintype "passive"))
    )
    (net (code "16") (name "Net-(Q1-C)") (class "Default")
      (node (ref "C4") (pin "2") (pinfunction "2_2") (pintype "passive"))
      (node (ref "J5") (pin "2") (pinfunction "2_2") (pintype "passive"))
      (node (ref "Q1") (pin "3") (pinfunction "C_3") (pintype "passive"))
      (node (ref "Q2") (pin "1") (pinfunction "GATE_1") (pintype "passive"))
      (node (ref "Q3") (pin "3") (pinfunction "SOURCE_3") (pintype "passive"))
      (node (ref "R3") (pin "1") (pinfunction "1_1") (pintype "passive"))
    )
    (net (code "17") (name "Net-(Q1-E)") (class "Default")
      (node (ref "J1") (pin "2") (pinfunction "2_2") (pintype "passive"))
      (node (ref "Q1") (pin "2") (pinfunction "E_2") (pintype "passive"))
      (node (ref "R1") (pin "1") (pinfunction "1_1") (pintype "passive"))
      (node (ref "R2") (pin "1") (pinfunction "1_1") (pintype "passive"))
      (node (ref "R3") (pin "2") (pinfunction "2_2") (pintype "passive"))
      (node (ref "R4") (pin "2") (pinfunction "2_2") (pintype "passive"))
      (node (ref "SW1") (pin "1") (pinfunction "1_1") (pintype "passive"))
    )
    (net (code "18") (name "Net-(Q2-DRAIN)") (class "Default")
      (node (ref "C1") (pin "1") (pinfunction "1_1") (pintype "passive"))
      (node (ref "C2") (pin "1") (pinfunction "1_1") (pintype "passive"))
      (node (ref "C3") (pin "1") (pinfunction "1_1") (pintype "passive"))
      (node (ref "J2") (pin "1") (pinfunction "1_1") (pintype "passive"))
      (node (ref "Q2") (pin "2") (pinfunction "DRAIN_2") (pintype "passive"))
    )
    (net (code "19") (name "Net-(Q3-DRAIN)") (class "Default")
      (node (ref "C7") (pin "2") (pinfunction "2_2") (pintype "passive"))
      (node (ref "J5") (pin "1") (pinfunction "1_1") (pintype "passive"))
      (node (ref "Q3") (pin "2") (pinfunction "DRAIN_2") (pintype "passive"))
      (node (ref "R8") (pin "2") (pinfunction "2_2") (pintype "passive"))
    )
    (net (code "20") (name "Net-(Q3-GATE)") (class "Default")
      (node (ref "Q3") (pin "1") (pinfunction "GATE_1") (pintype "passive"))
      (node (ref "R6") (pin "2") (pinfunction "2_2") (pintype "passive"))
    )
    (net (code "21") (name "Net-(Q4-B)") (class "Default")
      (node (ref "C5") (pin "2") (pinfunction "2_2") (pintype "passive"))
      (node (ref "Q4") (pin "1") (pinfunction "B_1") (pintype "passive"))
      (node (ref "R5") (pin "2") (pinfunction "2_2") (pintype "passive"))
    )
    (net (code "22") (name "Net-(Q4-C)") (class "Default")
      (node (ref "C4") (pin "1") (pinfunction "1_1") (pintype "passive"))
      (node (ref "C7") (pin "1") (pinfunction "1_1") (pintype "passive"))
      (node (ref "Q4") (pin "3") (pinfunction "C_3") (pintype "passive"))
      (node (ref "R4") (pin "1") (pinfunction "1_1") (pintype "passive"))
      (node (ref "R6") (pin "1") (pinfunction "1_1") (pintype "passive"))
    )
    (net (code "23") (name "Net-(Q4-E)") (class "Default")
      (node (ref "Q4") (pin "2") (pinfunction "E_2") (pintype "passive"))
      (node (ref "R7") (pin "2") (pinfunction "2_2") (pintype "passive"))
    )
    (net (code "24") (name "Net-(Q10-C)") (class "Default")
      (node (ref "Q10") (pin "2") (pinfunction "C_2") (pintype "passive"))
      (node (ref "Q9") (pin "2") (pinfunction "C_2") (pintype "passive"))
      (node (ref "R13") (pin "2") (pinfunction "2_2") (pintype "passive"))
      (node (ref "R14") (pin "2") (pinfunction "2_2") (pintype "passive"))
    )
    (net (code "25") (name "unconnected-(SW1-Pad3)") (class "Default")
      (node (ref "SW1") (pin "3") (pinfunction "3_3") (pintype "passive+no_connect"))
    )
  )
)
